# ULN2003.net
KiCad netlist of a schematic drawn in Altium Designer
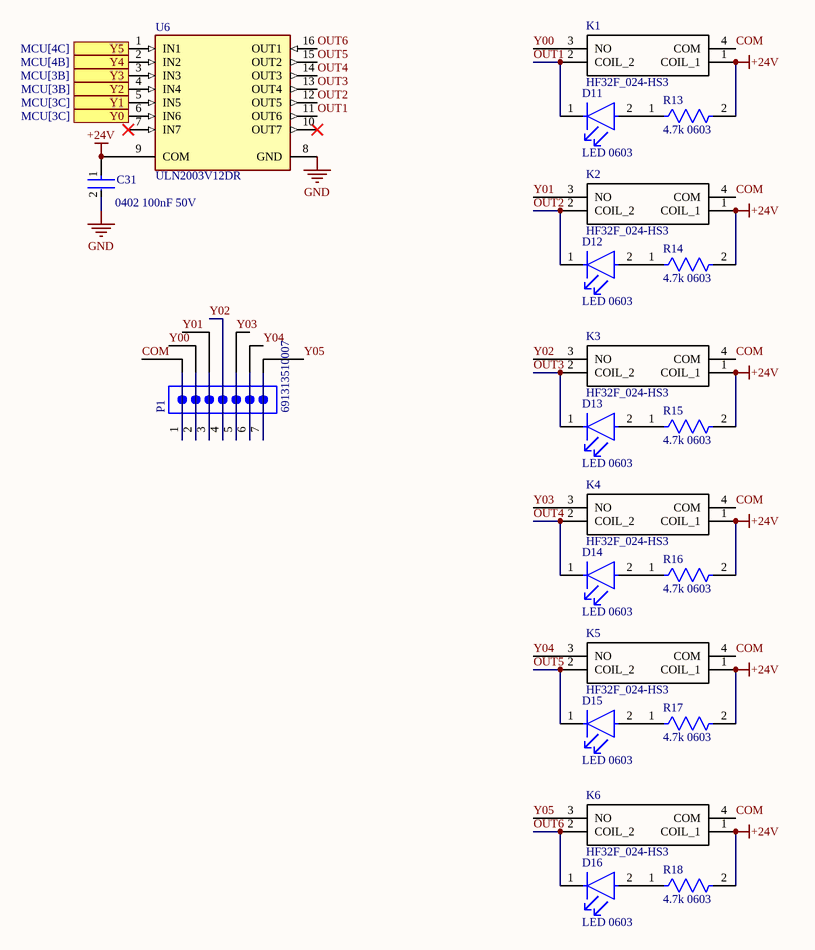
[diagram p0: ULN2003.SchDoc]

(export (version "E")
  (design (tool "Eeschema 10.0.6"))
  (components
    (comp (ref "C31")
      (value "0402 100nF 50V")
      (footprint "FP-0402B104K500CT-IPC_C")
      (description "CAP CER 0.1UF 50V X7R 0402")
      (fields (field (name "TOLERANCE") "10%"))
      (libsource (lib "Altium Content Vault") (part "11868f565c42a9108669ba33697ecf6"))
    )
    (comp (ref "D11")
      (value "LED 0603")
      (footprint "FP-LSM0603453V-MFG")
      (description "LSM0603453V LED SM 0603 3V -/1000/-mcd Green")
      (libsource (lib "Altium Content Vault") (part "8706943c75ba83719d021d2fdc84c58"))
    )
    (comp (ref "D12")
      (value "LED 0603")
      (footprint "FP-LSM0603453V-MFG")
      (description "LSM0603453V LED SM 0603 3V -/1000/-mcd Green")
      (libsource (lib "Altium Content Vault") (part "8706943c75ba83719d021d2fdc84c58"))
    )
    (comp (ref "D13")
      (value "LED 0603")
      (footprint "FP-LSM0603453V-MFG")
      (description "LSM0603453V LED SM 0603 3V -/1000/-mcd Green")
      (libsource (lib "Altium Content Vault") (part "8706943c75ba83719d021d2fdc84c58"))
    )
    (comp (ref "D14")
      (value "LED 0603")
      (footprint "FP-LSM0603453V-MFG")
      (description "LSM0603453V LED SM 0603 3V -/1000/-mcd Green")
      (libsource (lib "Altium Content Vault") (part "8706943c75ba83719d021d2fdc84c58"))
    )
    (comp (ref "D15")
      (value "LED 0603")
      (footprint "FP-LSM0603453V-MFG")
      (description "LSM0603453V LED SM 0603 3V -/1000/-mcd Green")
      (libsource (lib "Altium Content Vault") (part "8706943c75ba83719d021d2fdc84c58"))
    )
    (comp (ref "D16")
      (value "LED 0603")
      (footprint "FP-LSM0603453V-MFG")
      (description "LSM0603453V LED SM 0603 3V -/1000/-mcd Green")
      (libsource (lib "Altium Content Vault") (part "8706943c75ba83719d021d2fdc84c58"))
    )
    (comp (ref "K1")
      (value "HF32F_024-HS3")
      (footprint "PcbLib1:HF32F024HS3")
      (description "Relay or Contactor")
      (fields (field (name "MANUFACTURER_PART_NUMBER") "HF32F/024-HS3"))
      (libsource (lib "Schlib1") (part "HF32F_024-HS3"))
    )
    (comp (ref "K2")
      (value "HF32F_024-HS3")
      (footprint "PcbLib1:HF32F024HS3")
      (description "Relay or Contactor")
      (fields (field (name "MANUFACTURER_PART_NUMBER") "HF32F/024-HS3"))
      (libsource (lib "Schlib1") (part "HF32F_024-HS3"))
    )
    (comp (ref "K3")
      (value "HF32F_024-HS3")
      (footprint "PcbLib1:HF32F024HS3")
      (description "Relay or Contactor")
      (fields (field (name "MANUFACTURER_PART_NUMBER") "HF32F/024-HS3"))
      (libsource (lib "Schlib1") (part "HF32F_024-HS3"))
    )
    (comp (ref "K4")
      (value "HF32F_024-HS3")
      (footprint "PcbLib1:HF32F024HS3")
      (description "Relay or Contactor")
      (fields (field (name "MANUFACTURER_PART_NUMBER") "HF32F/024-HS3"))
      (libsource (lib "Schlib1") (part "HF32F_024-HS3"))
    )
    (comp (ref "K5")
      (value "HF32F_024-HS3")
      (footprint "PcbLib1:HF32F024HS3")
      (description "Relay or Contactor")
      (fields (field (name "MANUFACTURER_PART_NUMBER") "HF32F/024-HS3"))
      (libsource (lib "Schlib1") (part "HF32F_024-HS3"))
    )
    (comp (ref "K6")
      (value "HF32F_024-HS3")
      (footprint "PcbLib1:HF32F024HS3")
      (description "Relay or Contactor")
      (fields (field (name "MANUFACTURER_PART_NUMBER") "HF32F/024-HS3"))
      (libsource (lib "Schlib1") (part "HF32F_024-HS3"))
    )
    (comp (ref "P1")
      (value "691313510007")
      (footprint "691313510007")
      (description "Terminal Block, 5.08MM Pitch, Close Horizontal Pcb Header, 300VAC, 7 Pins")
      (libsource (lib "Altium Content Vault") (part "TBL - 1R - 07P - Male"))
    )
    (comp (ref "R13")
      (value "4.7k 0603")
      (footprint "FP-AC0603-MFG")
      (description "RES 4.7kΩ 1.00% 0.2W 0603")
      (libsource (lib "Altium Content Vault") (part "1029c3af85768c4190bb7ad29bc67b5"))
    )
    (comp (ref "R14")
      (value "4.7k 0603")
      (footprint "FP-AC0603-MFG")
      (description "RES 4.7kΩ 1.00% 0.2W 0603")
      (libsource (lib "Altium Content Vault") (part "1029c3af85768c4190bb7ad29bc67b5"))
    )
    (comp (ref "R15")
      (value "4.7k 0603")
      (footprint "FP-AC0603-MFG")
      (description "RES 4.7kΩ 1.00% 0.2W 0603")
      (libsource (lib "Altium Content Vault") (part "1029c3af85768c4190bb7ad29bc67b5"))
    )
    (comp (ref "R16")
      (value "4.7k 0603")
      (footprint "FP-AC0603-MFG")
      (description "RES 4.7kΩ 1.00% 0.2W 0603")
      (libsource (lib "Altium Content Vault") (part "1029c3af85768c4190bb7ad29bc67b5"))
    )
    (comp (ref "R17")
      (value "4.7k 0603")
      (footprint "FP-AC0603-MFG")
      (description "RES 4.7kΩ 1.00% 0.2W 0603")
      (libsource (lib "Altium Content Vault") (part "1029c3af85768c4190bb7ad29bc67b5"))
    )
    (comp (ref "R18")
      (value "4.7k 0603")
      (footprint "FP-AC0603-MFG")
      (description "RES 4.7kΩ 1.00% 0.2W 0603")
      (libsource (lib "Altium Content Vault") (part "1029c3af85768c4190bb7ad29bc67b5"))
    )
    (comp (ref "U6")
      (value "ULN2003V12DR")
      (footprint "FP-D0016A-MFG")
      (description "MOSFET 7CH 16SOIC")
      (libsource (lib "Altium Content Vault") (part "1bf5c18f3aeaca83cb90dec63c1b343"))
    )
  )
  (nets
    (net (code "1") (name "+24V") (class "Default")
      (node (ref "C31") (pin "1") (pinfunction "1_1") (pintype "passive"))
      (node (ref "K1") (pin "1") (pinfunction "COIL_1_1") (pintype "passive"))
      (node (ref "K2") (pin "1") (pinfunction "COIL_1_1") (pintype "passive"))
      (node (ref "K3") (pin "1") (pinfunction "COIL_1_1") (pintype "passive"))
      (node (ref "K4") (pin "1") (pinfunction "COIL_1_1") (pintype "passive"))
      (node (ref "K5") (pin "1") (pinfunction "COIL_1_1") (pintype "passive"))
      (node (ref "K6") (pin "1") (pinfunction "COIL_1_1") (pintype "passive"))
      (node (ref "R13") (pin "2") (pinfunction "2_2") (pintype "passive"))
      (node (ref "R14") (pin "2") (pinfunction "2_2") (pintype "passive"))
      (node (ref "R15") (pin "2") (pinfunction "2_2") (pintype "passive"))
      (node (ref "R16") (pin "2") (pinfunction "2_2") (pintype "passive"))
      (node (ref "R17") (pin "2") (pinfunction "2_2") (pintype "passive"))
      (node (ref "R18") (pin "2") (pinfunction "2_2") (pintype "passive"))
      (node (ref "U6") (pin "9") (pinfunction "COM_9") (pintype "passive"))
    )
    (net (code "2") (name "/COM") (class "Default")
      (node (ref "K1") (pin "4") (pinfunction "COM_4") (pintype "passive"))
      (node (ref "K2") (pin "4") (pinfunction "COM_4") (pintype "passive"))
      (node (ref "K3") (pin "4") (pinfunction "COM_4") (pintype "passive"))
      (node (ref "K4") (pin "4") (pinfunction "COM_4") (pintype "passive"))
      (node (ref "K5") (pin "4") (pinfunction "COM_4") (pintype "passive"))
      (node (ref "K6") (pin "4") (pinfunction "COM_4") (pintype "passive"))
      (node (ref "P1") (pin "1") (pinfunction "1_1") (pintype "passive"))
    )
    (net (code "3") (name "/OUT1") (class "Default")
      (node (ref "D11") (pin "1") (pinfunction "C_1") (pintype "passive"))
      (node (ref "K1") (pin "2") (pinfunction "COIL_2_2") (pintype "passive"))
      (node (ref "U6") (pin "11") (pinfunction "OUT6_11") (pintype "output"))
    )
    (net (code "4") (name "/OUT2") (class "Default")
      (node (ref "D12") (pin "1") (pinfunction "C_1") (pintype "passive"))
      (node (ref "K2") (pin "2") (pinfunction "COIL_2_2") (pintype "passive"))
      (node (ref "U6") (pin "12") (pinfunction "OUT5_12") (pintype "output"))
    )
    (net (code "5") (name "/OUT3") (class "Default")
      (node (ref "D13") (pin "1") (pinfunction "C_1") (pintype "passive"))
      (node (ref "K3") (pin "2") (pinfunction "COIL_2_2") (pintype "passive"))
      (node (ref "U6") (pin "13") (pinfunction "OUT4_13") (pintype "output"))
    )
    (net (code "6") (name "/OUT4") (class "Default")
      (node (ref "D14") (pin "1") (pinfunction "C_1") (pintype "passive"))
      (node (ref "K4") (pin "2") (pinfunction "COIL_2_2") (pintype "passive"))
      (node (ref "U6") (pin "14") (pinfunction "OUT3_14") (pintype "output"))
    )
    (net (code "7") (name "/OUT5") (class "Default")
      (node (ref "D15") (pin "1") (pinfunction "C_1") (pintype "passive"))
      (node (ref "K5") (pin "2") (pinfunction "COIL_2_2") (pintype "passive"))
      (node (ref "U6") (pin "15") (pinfunction "OUT2_15") (pintype "output"))
    )
    (net (code "8") (name "/OUT6") (class "Default")
      (node (ref "D16") (pin "1") (pinfunction "C_1") (pintype "passive"))
      (node (ref "K6") (pin "2") (pinfunction "COIL_2_2") (pintype "passive"))
      (node (ref "U6") (pin "16") (pinfunction "OUT1_16") (pintype "input"))
    )
    (net (code "9") (name "/Y0") (class "Default")
      (node (ref "U6") (pin "6") (pinfunction "IN6_6") (pintype "input"))
    )
    (net (code "10") (name "/Y00") (class "Default")
      (node (ref "K1") (pin "3") (pinfunction "NO_3") (pintype "passive"))
      (node (ref "P1") (pin "2") (pinfunction "2_2") (pintype "passive"))
    )
    (net (code "11") (name "/Y1") (class "Default")
      (node (ref "U6") (pin "5") (pinfunction "IN5_5") (pintype "input"))
    )
    (net (code "12") (name "/Y01") (class "Default")
      (node (ref "K2") (pin "3") (pinfunction "NO_3") (pintype "passive"))
      (node (ref "P1") (pin "3") (pinfunction "3_3") (pintype "passive"))
    )
    (net (code "13") (name "/Y2") (class "Default")
      (node (ref "U6") (pin "4") (pinfunction "IN4_4") (pintype "input"))
    )
    (net (code "14") (name "/Y02") (class "Default")
      (node (ref "K3") (pin "3") (pinfunction "NO_3") (pintype "passive"))
      (node (ref "P1") (pin "4") (pinfunction "4_4") (pintype "passive"))
    )
    (net (code "15") (name "/Y3") (class "Default")
      (node (ref "U6") (pin "3") (pinfunction "IN3_3") (pintype "input"))
    )
    (net (code "16") (name "/Y03") (class "Default")
      (node (ref "K4") (pin "3") (pinfunction "NO_3") (pintype "passive"))
      (node (ref "P1") (pin "5") (pinfunction "5_5") (pintype "passive"))
    )
    (net (code "17") (name "/Y4") (class "Default")
      (node (ref "U6") (pin "2") (pinfunction "IN2_2") (pintype "input"))
    )
    (net (code "18") (name "/Y04") (class "Default")
      (node (ref "K5") (pin "3") (pinfunction "NO_3") (pintype "passive"))
      (node (ref "P1") (pin "6") (pinfunction "6_6") (pintype "passive"))
    )
    (net (code "19") (name "/Y5") (class "Default")
      (node (ref "U6") (pin "1") (pinfunction "IN1_1") (pintype "input"))
    )
    (net (code "20") (name "/Y05") (class "Default")
      (node (ref "K6") (pin "3") (pinfunction "NO_3") (pintype "passive"))
      (node (ref "P1") (pin "7") (pinfunction "7_7") (pintype "passive"))
    )
    (net (code "21") (name "GND") (class "Default")
      (node (ref "C31") (pin "2") (pinfunction "2_2") (pintype "passive"))
      (node (ref "U6") (pin "8") (pinfunction "GND_8") (pintype "power_in"))
    )
    (net (code "22") (name "Net-(D11-A)") (class "Default")
      (node (ref "D11") (pin "2") (pinfunction "A_2") (pintype "passive"))
      (node (ref "R13") (pin "1") (pinfunction "1_1") (pintype "passive"))
    )
    (net (code "23") (name "Net-(D12-A)") (class "Default")
      (node (ref "D12") (pin "2") (pinfunction "A_2") (pintype "passive"))
      (node (ref "R14") (pin "1") (pinfunction "1_1") (pintype "passive"))
    )
    (net (code "24") (name "Net-(D13-A)") (class "Default")
      (node (ref "D13") (pin "2") (pinfunction "A_2") (pintype "passive"))
      (node (ref "R15") (pin "1") (pinfunction "1_1") (pintype "passive"))
    )
    (net (code "25") (name "Net-(D14-A)") (class "Default")
      (node (ref "D14") (pin "2") (pinfunction "A_2") (pintype "passive"))
      (node (ref "R16") (pin "1") (pinfunction "1_1") (pintype "passive"))
    )
    (net (code "26") (name "Net-(D15-A)") (class "Default")
      (node (ref "D15") (pin "2") (pinfunction "A_2") (pintype "passive"))
      (node (ref "R17") (pin "1") (pinfunction "1_1") (pintype "passive"))
    )
    (net (code "27") (name "Net-(D16-A)") (class "Default")
      (node (ref "D16") (pin "2") (pinfunction "A_2") (pintype "passive"))
      (node (ref "R18") (pin "1") (pinfunction "1_1") (pintype "passive"))
    )
    (net (code "28") (name "unconnected-(U6-IN7-Pad7)") (class "Default")
      (node (ref "U6") (pin "7") (pinfunction "IN7_7") (pintype "input+no_connect"))
    )
    (net (code "29") (name "unconnected-(U6-OUT7-Pad10)") (class "Default")
      (node (ref "U6") (pin "10") (pinfunction "OUT7_10") (pintype "output+no_connect"))
    )
  )
)
